# ETHERNET.net
KiCad netlist of a schematic drawn in Altium Designer
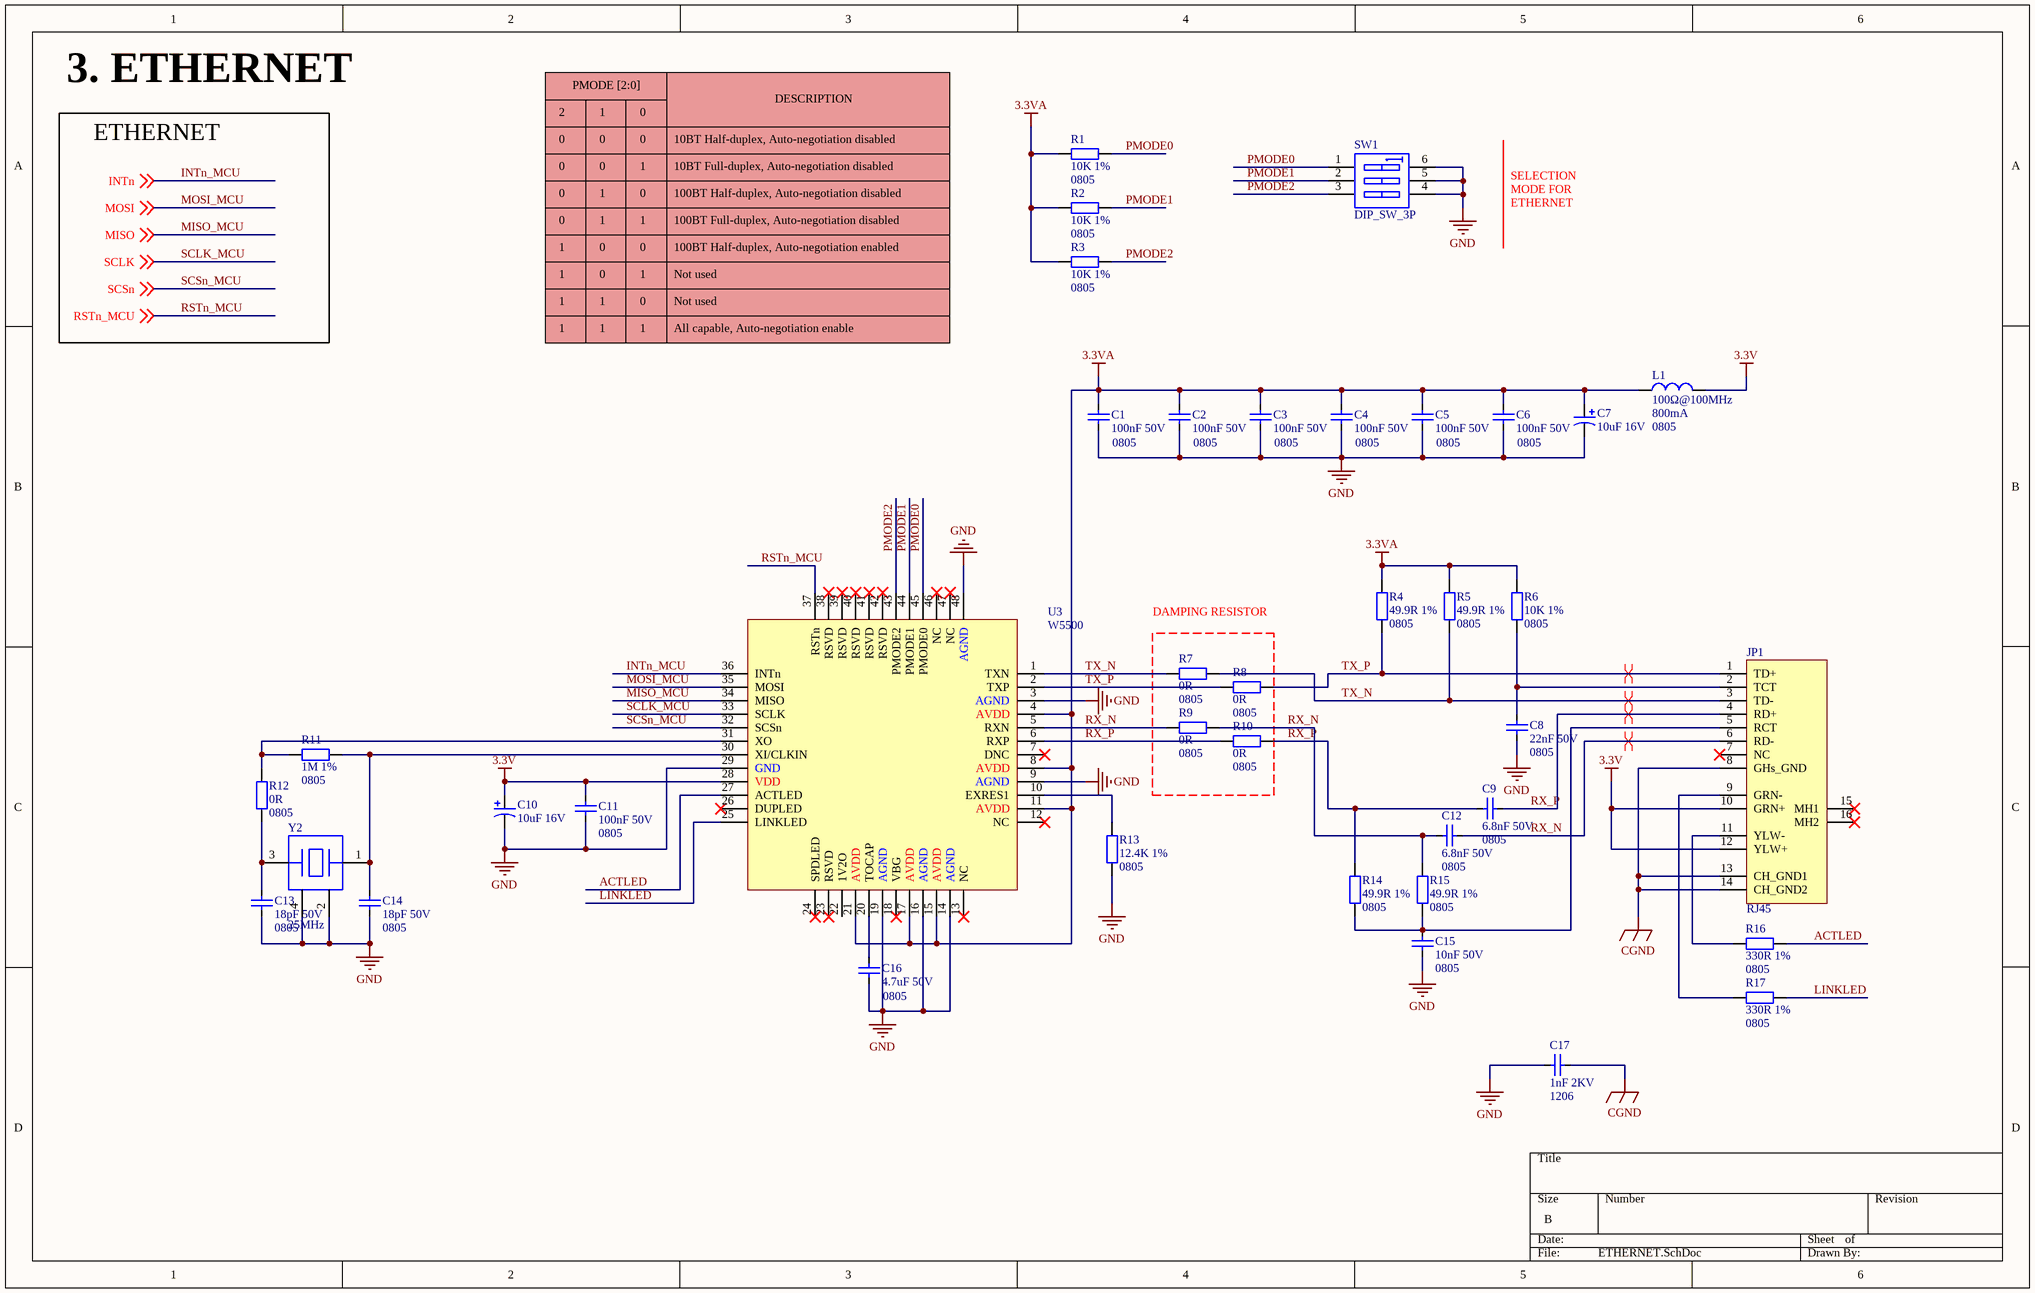
[diagram p0: ETHERNET.SchDoc]

(export (version "E")
  (design (tool "Eeschema 10.0.6"))
  (components
    (comp (ref "C1")
      (value "100nF 50V")
      (footprint "CAP_SMD_0805")
      (description "0.1 µF ±10% 50V Ceramic Capacitor X7R 0805 (2012 Metric)")
      (fields
        (field (name "MANUFACTURER") "YAGEO")
        (field (name "MANUFACTURE PART NUMBER") "CC0805KRX7R9BB104")
        (field (name "SIZE") "0805")
      )
      (libsource (lib "Capacitors") (part "C0805_MLCC_100nF_50V"))
    )
    (comp (ref "C2")
      (value "100nF 50V")
      (footprint "CAP_SMD_0805")
      (description "0.1 µF ±10% 50V Ceramic Capacitor X7R 0805 (2012 Metric)")
      (fields
        (field (name "MANUFACTURER") "YAGEO")
        (field (name "MANUFACTURE PART NUMBER") "CC0805KRX7R9BB104")
        (field (name "SIZE") "0805")
      )
      (libsource (lib "Capacitors") (part "C0805_MLCC_100nF_50V"))
    )
    (comp (ref "C3")
      (value "100nF 50V")
      (footprint "CAP_SMD_0805")
      (description "0.1 µF ±10% 50V Ceramic Capacitor X7R 0805 (2012 Metric)")
      (fields
        (field (name "MANUFACTURER") "YAGEO")
        (field (name "MANUFACTURE PART NUMBER") "CC0805KRX7R9BB104")
        (field (name "SIZE") "0805")
      )
      (libsource (lib "Capacitors") (part "C0805_MLCC_100nF_50V"))
    )
    (comp (ref "C4")
      (value "100nF 50V")
      (footprint "CAP_SMD_0805")
      (description "0.1 µF ±10% 50V Ceramic Capacitor X7R 0805 (2012 Metric)")
      (fields
        (field (name "MANUFACTURER") "YAGEO")
        (field (name "MANUFACTURE PART NUMBER") "CC0805KRX7R9BB104")
        (field (name "SIZE") "0805")
      )
      (libsource (lib "Capacitors") (part "C0805_MLCC_100nF_50V"))
    )
    (comp (ref "C5")
      (value "100nF 50V")
      (footprint "CAP_SMD_0805")
      (description "0.1 µF ±10% 50V Ceramic Capacitor X7R 0805 (2012 Metric)")
      (fields
        (field (name "MANUFACTURER") "YAGEO")
        (field (name "MANUFACTURE PART NUMBER") "CC0805KRX7R9BB104")
        (field (name "SIZE") "0805")
      )
      (libsource (lib "Capacitors") (part "C0805_MLCC_100nF_50V"))
    )
    (comp (ref "C6")
      (value "100nF 50V")
      (footprint "CAP_SMD_0805")
      (description "0.1 µF ±10% 50V Ceramic Capacitor X7R 0805 (2012 Metric)")
      (fields
        (field (name "MANUFACTURER") "YAGEO")
        (field (name "MANUFACTURE PART NUMBER") "CC0805KRX7R9BB104")
        (field (name "SIZE") "0805")
      )
      (libsource (lib "Capacitors") (part "C0805_MLCC_100nF_50V"))
    )
    (comp (ref "C7")
      (value "10uF 16V")
      (footprint "CAP-ALU-SMD-C")
      (description "10 µF 16 V Aluminum - Polymer Capacitors Radial, Can - SMD 30mOhm 2000 Hrs @ 105°C")
      (fields
        (field (name "MANUFACTURER") "Würth Elektronik")
        (field (name "MANUFACTURE PART NUMBER") "875105359001")
      )
      (libsource (lib "") (part "C_ALU_10uF_16V_1"))
    )
    (comp (ref "C8")
      (value "22nF 50V")
      (footprint "CAP_SMD_0805")
      (description "0.022 µF ±5% 50V Ceramic Capacitor C0G, NP0 0805 (2012 Metric)")
      (fields
        (field (name "MANUFACTURER") "TDK Corporation")
        (field (name "MANUFACTURE PART NUMBER") "CGA4J2C0G1H223J125AA")
        (field (name "SIZE") "0805")
      )
      (libsource (lib "Capacitors") (part "C0805_MLCC_22nF_50V"))
    )
    (comp (ref "C9")
      (value "6.8nF 50V")
      (footprint "CAP_SMD_0805")
      (description "6800 pF ±10% 50V Ceramic Capacitor X7R 0805 (2012 Metric)")
      (fields
        (field (name "MANUFACTURER") "KEMET")
        (field (name "MANUFACTURE PART NUMBER") "C0805C682K5RAC7800")
        (field (name "SIZE") "0805")
      )
      (libsource (lib "Capacitors") (part "C0805_MLCC_6.8nF_50V"))
    )
    (comp (ref "C10")
      (value "10uF 16V")
      (footprint "CAP-ALU-SMD-C")
      (description "10 µF 16 V Aluminum - Polymer Capacitors Radial, Can - SMD 30mOhm 2000 Hrs @ 105°C")
      (fields
        (field (name "MANUFACTURER") "Würth Elektronik")
        (field (name "MANUFACTURE PART NUMBER") "875105359001")
      )
      (libsource (lib "Capacitors") (part "C_ALU_10uF_16V"))
    )
    (comp (ref "C11")
      (value "100nF 50V")
      (footprint "CAP_SMD_0805")
      (description "0.1 µF ±10% 50V Ceramic Capacitor X7R 0805 (2012 Metric)")
      (fields
        (field (name "MANUFACTURER") "YAGEO")
        (field (name "MANUFACTURE PART NUMBER") "CC0805KRX7R9BB104")
        (field (name "SIZE") "0805")
      )
      (libsource (lib "Capacitors") (part "C0805_MLCC_100nF_50V"))
    )
    (comp (ref "C12")
      (value "6.8nF 50V")
      (footprint "CAP_SMD_0805")
      (description "6800 pF ±10% 50V Ceramic Capacitor X7R 0805 (2012 Metric)")
      (fields
        (field (name "MANUFACTURER") "KEMET")
        (field (name "MANUFACTURE PART NUMBER") "C0805C682K5RAC7800")
        (field (name "SIZE") "0805")
      )
      (libsource (lib "Capacitors") (part "C0805_MLCC_6.8nF_50V"))
    )
    (comp (ref "C13")
      (value "18pF 50V")
      (footprint "CAP_SMD_0805")
      (description "Multilayer Ceramic Capacitors MLCC - SMD/SMT 50V 18pF C0G 0805 1%")
      (fields
        (field (name "MANUFACTURER") "KEMET")
        (field (name "MANUFACTURE PART NUMBER") "C0805C180F5GACTU")
        (field (name "SIZE") "0805")
      )
      (libsource (lib "Capacitors") (part "C0805_MLCC_18pF_50V"))
    )
    (comp (ref "C14")
      (value "18pF 50V")
      (footprint "CAP_SMD_0805")
      (description "Multilayer Ceramic Capacitors MLCC - SMD/SMT 50V 18pF C0G 0805 1%")
      (fields
        (field (name "MANUFACTURER") "KEMET")
        (field (name "MANUFACTURE PART NUMBER") "C0805C180F5GACTU")
        (field (name "SIZE") "0805")
      )
      (libsource (lib "Capacitors") (part "C0805_MLCC_18pF_50V"))
    )
    (comp (ref "C15")
      (value "10nF 50V")
      (footprint "CAP_SMD_0805")
      (description "10000 pF ±10% 50V Ceramic Capacitor X7R 0805 (2012 Metric)")
      (fields
        (field (name "MANUFACTURER") "Samsung Electro-Mechanics")
        (field (name "MANUFACTURE PART NUMBER") "CL21B103KBANNNC")
        (field (name "SIZE") "0805")
      )
      (libsource (lib "Capacitors") (part "C0805_MLCC_10nF_50V"))
    )
    (comp (ref "C16")
      (value "4.7uF 50V")
      (footprint "CAP_SMD_0805")
      (description "4.7 µF ±10% 50V Ceramic Capacitor X5R 0805 (2012 Metric)")
      (fields
        (field (name "MANUFACTURER") "Samsung Electro-Mechanics")
        (field (name "MANUFACTURE PART NUMBER") "CL21A475KBQNNNE")
        (field (name "SIZE") "0805")
      )
      (libsource (lib "Capacitors") (part "C0805_MLCC_4.7uF_50V"))
    )
    (comp (ref "C17")
      (value "1nF 2KV")
      (footprint "CAP_SMD_0805")
      (description "1000 pF ±5% 2000V (2kV) Ceramic Capacitor X7R 1206 (3216 Metric)")
      (fields
        (field (name "MANUFACTURER") "YAGEO")
        (field (name "MANUFACTURE PART NUMBER") "CC1206JKX7RDBB102")
        (field (name "SIZE") "1206")
      )
      (libsource (lib "Capacitors") (part "C1206_MLCC_1nF_2KV"))
    )
    (comp (ref "JP1")
      (value "RJ45")
      (footprint "RJ 45")
      (description "1 Port RJ45Through Hole 10/100 Base-T, AutoMDIX")
      (fields (field (name "MANUFACTURER") "WIZnet") (field (name "MANUFACTURE PART NUMBER") "1278-1052-ND"))
      (libsource (lib "Connectors") (part "RJ45"))
    )
    (comp (ref "L1")
      (value "100Ohms 100Mhz")
      (footprint "FB_0805")
      (fields
        (field (name "MANUFACTURER") "TAI-TECH")
        (field (name "MANUFACTURE PART NUMBER") "FCM2012KF-101T08")
        (field (name "IMPEDANCE @ FREQUENCY") "100Ω@100MHz")
        (field (name "CURRENT") "800mA")
        (field (name "SIZE") "0805")
      )
      (libsource (lib "Inductors") (part "FR_100Ohms_100Mhz"))
    )
    (comp (ref "R1")
      (value "10K 1%")
      (footprint "RES_SMD_0805")
      (description "10 kOhms ±1% 0.125W, 1/8W Chip Resistor 0805 (2012 Metric) Moisture Resistant Thick Film")
      (fields
        (field (name "MANUFACTURER") "YAGEO")
        (field (name "MANUFACTURE PART NUMBER") "RC0805FR-0710KL")
        (field (name "SIZE") "0805")
      )
      (libsource (lib "Resistors") (part "R0805_10K"))
    )
    (comp (ref "R2")
      (value "10K 1%")
      (footprint "RES_SMD_0805")
      (description "10 kOhms ±1% 0.125W, 1/8W Chip Resistor 0805 (2012 Metric) Moisture Resistant Thick Film")
      (fields
        (field (name "MANUFACTURER") "YAGEO")
        (field (name "MANUFACTURE PART NUMBER") "RC0805FR-0710KL")
        (field (name "SIZE") "0805")
      )
      (libsource (lib "Resistors") (part "R0805_10K"))
    )
    (comp (ref "R3")
      (value "10K 1%")
      (footprint "RES_SMD_0805")
      (description "10 kOhms ±1% 0.125W, 1/8W Chip Resistor 0805 (2012 Metric) Moisture Resistant Thick Film")
      (fields
        (field (name "MANUFACTURER") "YAGEO")
        (field (name "MANUFACTURE PART NUMBER") "RC0805FR-0710KL")
        (field (name "SIZE") "0805")
      )
      (libsource (lib "Resistors") (part "R0805_10K"))
    )
    (comp (ref "R4")
      (value "49.9R 1%")
      (footprint "RES_SMD_0805")
      (description "49.9 Ohms ±1% 0.125W, 1/8W Chip Resistor 0805 (2012 Metric) Automotive AEC-Q200 Thick Film")
      (fields
        (field (name "MANUFACTURER") "Stackpole Electronics Inc")
        (field (name "MANUFACTURE PART NUMBER") "RMCF0805FT49R9")
        (field (name "SIZE") "0805")
      )
      (libsource (lib "Resistors") (part "R0805_49.9R"))
    )
    (comp (ref "R5")
      (value "49.9R 1%")
      (footprint "RES_SMD_0805")
      (description "49.9 Ohms ±1% 0.125W, 1/8W Chip Resistor 0805 (2012 Metric) Automotive AEC-Q200 Thick Film")
      (fields
        (field (name "MANUFACTURER") "Stackpole Electronics Inc")
        (field (name "MANUFACTURE PART NUMBER") "RMCF0805FT49R9")
        (field (name "SIZE") "0805")
      )
      (libsource (lib "Resistors") (part "R0805_49.9R"))
    )
    (comp (ref "R6")
      (value "10K 1%")
      (footprint "RES_SMD_0805")
      (description "10 kOhms ±1% 0.125W, 1/8W Chip Resistor 0805 (2012 Metric) Moisture Resistant Thick Film")
      (fields
        (field (name "MANUFACTURER") "YAGEO")
        (field (name "MANUFACTURE PART NUMBER") "RC0805FR-0710KL")
        (field (name "SIZE") "0805")
      )
      (libsource (lib "Resistors") (part "R0805_10K"))
    )
    (comp (ref "R7")
      (value "0R")
      (footprint "RES_SMD_0805")
      (description "0 Ohms Jumper Chip Resistor 0805 (2012 Metric) Automotive AEC-Q200 Thick Film")
      (fields
        (field (name "MANUFACTURER") "Vishay Dale")
        (field (name "MANUFACTURE PART NUMBER") "CRCW08050000Z0EA")
        (field (name "SIZE") "0805")
      )
      (libsource (lib "Resistors") (part "R0805_0R"))
    )
    (comp (ref "R8")
      (value "0R")
      (footprint "RES_SMD_0805")
      (description "0 Ohms Jumper Chip Resistor 0805 (2012 Metric) Automotive AEC-Q200 Thick Film")
      (fields
        (field (name "MANUFACTURER") "Vishay Dale")
        (field (name "MANUFACTURE PART NUMBER") "CRCW08050000Z0EA")
        (field (name "SIZE") "0805")
      )
      (libsource (lib "Resistors") (part "R0805_0R"))
    )
    (comp (ref "R9")
      (value "0R")
      (footprint "RES_SMD_0805")
      (description "0 Ohms Jumper Chip Resistor 0805 (2012 Metric) Automotive AEC-Q200 Thick Film")
      (fields
        (field (name "MANUFACTURER") "Vishay Dale")
        (field (name "MANUFACTURE PART NUMBER") "CRCW08050000Z0EA")
        (field (name "SIZE") "0805")
      )
      (libsource (lib "Resistors") (part "R0805_0R"))
    )
    (comp (ref "R10")
      (value "0R")
      (footprint "RES_SMD_0805")
      (description "0 Ohms Jumper Chip Resistor 0805 (2012 Metric) Automotive AEC-Q200 Thick Film")
      (fields
        (field (name "MANUFACTURER") "Vishay Dale")
        (field (name "MANUFACTURE PART NUMBER") "CRCW08050000Z0EA")
        (field (name "SIZE") "0805")
      )
      (libsource (lib "Resistors") (part "R0805_0R"))
    )
    (comp (ref "R11")
      (value "1M 1%")
      (footprint "RES_SMD_0805")
      (description "1 MOhms ±1% 0.125W, 1/8W Chip Resistor 0805 (2012 Metric) Automotive AEC-Q200 Thick Film")
      (fields
        (field (name "MANUFACTURER") "Stackpole Electronics Inc")
        (field (name "MANUFACTURE PART NUMBER") "RMCF0805FT1M00")
        (field (name "SIZE") "0805")
      )
      (libsource (lib "Resistors") (part "R0805_1M"))
    )
    (comp (ref "R12")
      (value "0R")
      (footprint "RES_SMD_0805")
      (description "0 Ohms Jumper Chip Resistor 0805 (2012 Metric) Automotive AEC-Q200 Thick Film")
      (fields
        (field (name "MANUFACTURER") "Vishay Dale")
        (field (name "MANUFACTURE PART NUMBER") "CRCW08050000Z0EA")
        (field (name "SIZE") "0805")
      )
      (libsource (lib "Resistors") (part "R0805_0R"))
    )
    (comp (ref "R13")
      (value "12.4K 1%")
      (footprint "RES_SMD_0805")
      (description "12.4 kOhms ±1% 0.125W, 1/8W Chip Resistor 0805 (2012 Metric) Automotive AEC-Q200 Thick Film")
      (fields
        (field (name "MANUFACTURER") "Stackpole Electronics Inc")
        (field (name "MANUFACTURE PART NUMBER") "RMCF0805FT12K4")
        (field (name "SIZE") "0805")
      )
      (libsource (lib "Resistors") (part "R0805_12.4K"))
    )
    (comp (ref "R14")
      (value "49.9R 1%")
      (footprint "RES_SMD_0805")
      (description "49.9 Ohms ±1% 0.125W, 1/8W Chip Resistor 0805 (2012 Metric) Automotive AEC-Q200 Thick Film")
      (fields
        (field (name "MANUFACTURER") "Stackpole Electronics Inc")
        (field (name "MANUFACTURE PART NUMBER") "RMCF0805FT49R9")
        (field (name "SIZE") "0805")
      )
      (libsource (lib "Resistors") (part "R0805_49.9R"))
    )
    (comp (ref "R15")
      (value "49.9R 1%")
      (footprint "RES_SMD_0805")
      (description "49.9 Ohms ±1% 0.125W, 1/8W Chip Resistor 0805 (2012 Metric) Automotive AEC-Q200 Thick Film")
      (fields
        (field (name "MANUFACTURER") "Stackpole Electronics Inc")
        (field (name "MANUFACTURE PART NUMBER") "RMCF0805FT49R9")
        (field (name "SIZE") "0805")
      )
      (libsource (lib "Resistors") (part "R0805_49.9R"))
    )
    (comp (ref "R16")
      (value "330R 1%")
      (footprint "RES_SMD_0805")
      (description "330 Ohms ±1% 0.125W, 1/8W Chip Resistor 0805 (2012 Metric) Automotive AEC-Q200 Thick Film")
      (fields
        (field (name "MANUFACTURER") "Stackpole Electronics Inc")
        (field (name "MANUFACTURE PART NUMBER") "RMCF0805FT330R")
        (field (name "SIZE") "0805")
      )
      (libsource (lib "Resistors") (part "R0805_330R"))
    )
    (comp (ref "R17")
      (value "330R 1%")
      (footprint "RES_SMD_0805")
      (description "330 Ohms ±1% 0.125W, 1/8W Chip Resistor 0805 (2012 Metric) Automotive AEC-Q200 Thick Film")
      (fields
        (field (name "MANUFACTURER") "Stackpole Electronics Inc")
        (field (name "MANUFACTURE PART NUMBER") "RMCF0805FT330R")
        (field (name "SIZE") "0805")
      )
      (libsource (lib "Resistors") (part "R0805_330R"))
    )
    (comp (ref "SW1")
      (value "DIP_SW_3P")
      (footprint "DIPSWITCH3")
      (description "Dip Switch SPST 3 Position Through Hole Slide (Standard) Actuator 25mA 24VDC")
      (fields
        (field (name "MANUFACTURER") "CIT Relay and Switch")
        (field (name "MANUFACTURE PART NUMBER") "KG03E")
      )
      (libsource (lib "Button") (part "DIP_SW_3P"))
    )
    (comp (ref "U3")
      (value "W5500")
      (footprint "LQFP 48")
      (description "Ethernet ICs 3in1 Enet Controller TCP/IP +MAC+PHY")
      (fields (field (name "MANUFACTURER") "WIZnet"))
      (libsource (lib "ICs") (part "W5500"))
    )
    (comp (ref "Y2")
      (value "25MHz")
      (footprint "SMD-3225_4P")
      (description "3.3V HCMOS ±4.6ppm 25MHz SMD3225-4P Temperature Compensated Crystal Oscillators (TCXOs) ROHS")
      (fields
        (field (name "MANUFACTURER") "HCI")
        (field (name "MANUFACTURE PART NUMBER") "TC32H4-25.000-33GNDTNL")
      )
      (libsource (lib "Crystal") (part "C3225_25MHz"))
    )
  )
  (nets
    (net (code "1") (name "/ACTLED") (class "Default")
      (node (ref "R16") (pin "2") (pinfunction "2_2") (pintype "passive"))
      (node (ref "U3") (pin "27") (pinfunction "ACTLED_27") (pintype "passive"))
    )
    (net (code "2") (name "/LINKLED") (class "Default")
      (node (ref "R17") (pin "2") (pinfunction "2_2") (pintype "passive"))
      (node (ref "U3") (pin "25") (pinfunction "LINKLED_25") (pintype "passive"))
    )
    (net (code "3") (name "/PMODE0") (class "Default")
      (node (ref "R1") (pin "1") (pinfunction "1_1") (pintype "passive"))
      (node (ref "SW1") (pin "1") (pinfunction "A1_1") (pintype "passive"))
      (node (ref "U3") (pin "45") (pinfunction "PMODE0_45") (pintype "passive"))
    )
    (net (code "4") (name "/PMODE1") (class "Default")
      (node (ref "R2") (pin "1") (pinfunction "1_1") (pintype "passive"))
      (node (ref "SW1") (pin "2") (pinfunction "A2_2") (pintype "passive"))
      (node (ref "U3") (pin "44") (pinfunction "PMODE1_44") (pintype "passive"))
    )
    (net (code "5") (name "/PMODE2") (class "Default")
      (node (ref "R3") (pin "1") (pinfunction "1_1") (pintype "passive"))
      (node (ref "SW1") (pin "3") (pinfunction "A3_3") (pintype "passive"))
      (node (ref "U3") (pin "43") (pinfunction "PMODE2_43") (pintype "passive"))
    )
    (net (code "6") (name "/RX_N") (class "Default")
      (node (ref "C12") (pin "1") (pinfunction "1_1") (pintype "passive"))
      (node (ref "C12") (pin "2") (pinfunction "2_2") (pintype "passive"))
      (node (ref "JP1") (pin "6") (pinfunction "RD-_6") (pintype "passive"))
      (node (ref "R15") (pin "2") (pinfunction "2_2") (pintype "passive"))
      (node (ref "R9") (pin "1") (pinfunction "1_1") (pintype "passive"))
      (node (ref "R9") (pin "2") (pinfunction "2_2") (pintype "passive"))
      (node (ref "U3") (pin "5") (pinfunction "RXN_5") (pintype "passive"))
    )
    (net (code "7") (name "/RX_P") (class "Default")
      (node (ref "C9") (pin "1") (pinfunction "1_1") (pintype "passive"))
      (node (ref "C9") (pin "2") (pinfunction "2_2") (pintype "passive"))
      (node (ref "JP1") (pin "4") (pinfunction "RD+_4") (pintype "passive"))
      (node (ref "R10") (pin "1") (pinfunction "1_1") (pintype "passive"))
      (node (ref "R10") (pin "2") (pinfunction "2_2") (pintype "passive"))
      (node (ref "R14") (pin "2") (pinfunction "2_2") (pintype "passive"))
      (node (ref "U3") (pin "6") (pinfunction "RXP_6") (pintype "passive"))
    )
    (net (code "8") (name "/TX_N") (class "Default")
      (node (ref "JP1") (pin "3") (pinfunction "TD-_3") (pintype "passive"))
      (node (ref "R5") (pin "1") (pinfunction "1_1") (pintype "passive"))
      (node (ref "R7") (pin "1") (pinfunction "1_1") (pintype "passive"))
      (node (ref "R7") (pin "2") (pinfunction "2_2") (pintype "passive"))
      (node (ref "U3") (pin "1") (pinfunction "TXN_1") (pintype "passive"))
    )
    (net (code "9") (name "/TX_P") (class "Default")
      (node (ref "JP1") (pin "1") (pinfunction "TD+_1") (pintype "passive"))
      (node (ref "R4") (pin "1") (pinfunction "1_1") (pintype "passive"))
      (node (ref "R8") (pin "1") (pinfunction "1_1") (pintype "passive"))
      (node (ref "R8") (pin "2") (pinfunction "2_2") (pintype "passive"))
      (node (ref "U3") (pin "2") (pinfunction "TXP_2") (pintype "passive"))
    )
    (net (code "10") (name "3.3V") (class "Default")
      (node (ref "C10") (pin "1") (pinfunction "1_1") (pintype "passive"))
      (node (ref "C11") (pin "2") (pinfunction "2_2") (pintype "passive"))
      (node (ref "JP1") (pin "10") (pinfunction "GRN+_10") (pintype "passive"))
      (node (ref "JP1") (pin "12") (pinfunction "YLW+_12") (pintype "passive"))
      (node (ref "L1") (pin "2") (pinfunction "2_2") (pintype "passive"))
      (node (ref "U3") (pin "28") (pinfunction "VDD_28") (pintype "passive"))
    )
    (net (code "11") (name "3.3VA") (class "Default")
      (node (ref "C1") (pin "2") (pinfunction "2_2") (pintype "passive"))
      (node (ref "C2") (pin "2") (pinfunction "2_2") (pintype "passive"))
      (node (ref "C3") (pin "2") (pinfunction "2_2") (pintype "passive"))
      (node (ref "C4") (pin "2") (pinfunction "2_2") (pintype "passive"))
      (node (ref "C5") (pin "2") (pinfunction "2_2") (pintype "passive"))
      (node (ref "C6") (pin "2") (pinfunction "2_2") (pintype "passive"))
      (node (ref "C7") (pin "1") (pinfunction "1_1") (pintype "passive"))
      (node (ref "L1") (pin "1") (pinfunction "1_1") (pintype "passive"))
      (node (ref "R1") (pin "2") (pinfunction "2_2") (pintype "passive"))
      (node (ref "R2") (pin "2") (pinfunction "2_2") (pintype "passive"))
      (node (ref "R3") (pin "2") (pinfunction "2_2") (pintype "passive"))
      (node (ref "R4") (pin "2") (pinfunction "2_2") (pintype "passive"))
      (node (ref "R5") (pin "2") (pinfunction "2_2") (pintype "passive"))
      (node (ref "R6") (pin "2") (pinfunction "2_2") (pintype "passive"))
      (node (ref "U3") (pin "11") (pinfunction "AVDD_11") (pintype "passive"))
      (node (ref "U3") (pin "15") (pinfunction "AVDD_15") (pintype "passive"))
      (node (ref "U3") (pin "17") (pinfunction "AVDD_17") (pintype "passive"))
      (node (ref "U3") (pin "21") (pinfunction "AVDD_21") (pintype "passive"))
      (node (ref "U3") (pin "4") (pinfunction "AVDD_4") (pintype "passive"))
      (node (ref "U3") (pin "8") (pinfunction "AVDD_8") (pintype "passive"))
    )
    (net (code "12") (name "CGND") (class "Default")
      (node (ref "C17") (pin "2") (pinfunction "2_2") (pintype "passive"))
      (node (ref "JP1") (pin "13") (pinfunction "CH_GND1_13") (pintype "passive"))
      (node (ref "JP1") (pin "14") (pinfunction "CH_GND2_14") (pintype "passive"))
      (node (ref "JP1") (pin "8") (pinfunction "GHs_GND_8") (pintype "passive"))
    )
    (net (code "13") (name "GND") (class "Default")
      (node (ref "C1") (pin "1") (pinfunction "1_1") (pintype "passive"))
      (node (ref "C10") (pin "2") (pinfunction "2_2") (pintype "passive"))
      (node (ref "C11") (pin "1") (pinfunction "1_1") (pintype "passive"))
      (node (ref "C13") (pin "1") (pinfunction "1_1") (pintype "passive"))
      (node (ref "C14") (pin "1") (pinfunction "1_1") (pintype "passive"))
      (node (ref "C15") (pin "1") (pinfunction "1_1") (pintype "passive"))
      (node (ref "C16") (pin "1") (pinfunction "1_1") (pintype "passive"))
      (node (ref "C17") (pin "1") (pinfunction "1_1") (pintype "passive"))
      (node (ref "C2") (pin "1") (pinfunction "1_1") (pintype "passive"))
      (node (ref "C3") (pin "1") (pinfunction "1_1") (pintype "passive"))
      (node (ref "C4") (pin "1") (pinfunction "1_1") (pintype "passive"))
      (node (ref "C5") (pin "1") (pinfunction "1_1") (pintype "passive"))
      (node (ref "C6") (pin "1") (pinfunction "1_1") (pintype "passive"))
      (node (ref "C7") (pin "2") (pinfunction "2_2") (pintype "passive"))
      (node (ref "C8") (pin "1") (pinfunction "1_1") (pintype "passive"))
      (node (ref "R13") (pin "1") (pinfunction "1_1") (pintype "passive"))
      (node (ref "SW1") (pin "4") (pinfunction "B3_4") (pintype "passive"))
      (node (ref "SW1") (pin "5") (pinfunction "B2_5") (pintype "passive"))
      (node (ref "SW1") (pin "6") (pinfunction "B1_6") (pintype "passive"))
      (node (ref "U3") (pin "14") (pinfunction "AGND_14") (pintype "passive"))
      (node (ref "U3") (pin "16") (pinfunction "AGND_16") (pintype "passive"))
      (node (ref "U3") (pin "19") (pinfunction "AGND_19") (pintype "passive"))
      (node (ref "U3") (pin "29") (pinfunction "GND_29") (pintype "passive"))
      (node (ref "U3") (pin "3") (pinfunction "AGND_3") (pintype "passive"))
      (node (ref "U3") (pin "48") (pinfunction "AGND_48") (pintype "passive"))
      (node (ref "U3") (pin "9") (pinfunction "AGND_9") (pintype "passive"))
      (node (ref "Y2") (pin "2") (pinfunction "2_2") (pintype "passive"))
      (node (ref "Y2") (pin "4") (pinfunction "4_4") (pintype "passive"))
    )
    (net (code "14") (name "INTn") (class "Default")
      (node (ref "U3") (pin "36") (pinfunction "INTn_36") (pintype "passive"))
    )
    (net (code "15") (name "MISO") (class "Default")
      (node (ref "U3") (pin "34") (pinfunction "MISO_34") (pintype "passive"))
    )
    (net (code "16") (name "MOSI") (class "Default")
      (node (ref "U3") (pin "35") (pinfunction "MOSI_35") (pintype "passive"))
    )
    (net (code "17") (name "Net-(C13-Pad2)") (class "Default")
      (node (ref "C13") (pin "2") (pinfunction "2_2") (pintype "passive"))
      (node (ref "R12") (pin "1") (pinfunction "1_1") (pintype "passive"))
      (node (ref "Y2") (pin "3") (pinfunction "3_3") (pintype "passive"))
    )
    (net (code "18") (name "Net-(JP1-GRN-)") (class "Default")
      (node (ref "JP1") (pin "9") (pinfunction "GRN-_9") (pintype "passive"))
      (node (ref "R17") (pin "1") (pinfunction "1_1") (pintype "passive"))
    )
    (net (code "19") (name "Net-(JP1-RCT)") (class "Default")
      (node (ref "C15") (pin "2") (pinfunction "2_2") (pintype "passive"))
      (node (ref "JP1") (pin "5") (pinfunction "RCT_5") (pintype "passive"))
      (node (ref "R14") (pin "1") (pinfunction "1_1") (pintype "passive"))
      (node (ref "R15") (pin "1") (pinfunction "1_1") (pintype "passive"))
    )
    (net (code "20") (name "Net-(JP1-TCT)") (class "Default")
      (node (ref "C8") (pin "2") (pinfunction "2_2") (pintype "passive"))
      (node (ref "JP1") (pin "2") (pinfunction "TCT_2") (pintype "passive"))
      (node (ref "R6") (pin "1") (pinfunction "1_1") (pintype "passive"))
    )
    (net (code "21") (name "Net-(JP1-YLW-)") (class "Default")
      (node (ref "JP1") (pin "11") (pinfunction "YLW-_11") (pintype "passive"))
      (node (ref "R16") (pin "1") (pinfunction "1_1") (pintype "passive"))
    )
    (net (code "22") (name "Net-(U3-EXRES1)") (class "Default")
      (node (ref "R13") (pin "2") (pinfunction "2_2") (pintype "passive"))
      (node (ref "U3") (pin "10") (pinfunction "EXRES1_10") (pintype "passive"))
    )
    (net (code "23") (name "Net-(U3-TOCAP)") (class "Default")
      (node (ref "C16") (pin "2") (pinfunction "2_2") (pintype "passive"))
      (node (ref "U3") (pin "20") (pinfunction "TOCAP_20") (pintype "passive"))
    )
    (net (code "24") (name "Net-(U3-XI{slash}CLKIN)") (class "Default")
      (node (ref "C14") (pin "2") (pinfunction "2_2") (pintype "passive"))
      (node (ref "R11") (pin "2") (pinfunction "2_2") (pintype "passive"))
      (node (ref "U3") (pin "30") (pinfunction "XI/CLKIN_30") (pintype "passive"))
      (node (ref "Y2") (pin "1") (pinfunction "1_1") (pintype "passive"))
    )
    (net (code "25") (name "Net-(U3-XO)") (class "Default")
      (node (ref "R11") (pin "1") (pinfunction "1_1") (pintype "passive"))
      (node (ref "R12") (pin "2") (pinfunction "2_2") (pintype "passive"))
      (node (ref "U3") (pin "31") (pinfunction "XO_31") (pintype "passive"))
    )
    (net (code "26") (name "RSTn_MCU") (class "Default")
      (node (ref "U3") (pin "37") (pinfunction "RSTn_37") (pintype "passive"))
    )
    (net (code "27") (name "SCLK") (class "Default")
      (node (ref "U3") (pin "33") (pinfunction "SCLK_33") (pintype "passive"))
    )
    (net (code "28") (name "SCSn") (class "Default")
      (node (ref "U3") (pin "32") (pinfunction "SCSn_32") (pintype "passive"))
    )
    (net (code "29") (name "unconnected-(JP1-MH1-Pad15)") (class "Default")
      (node (ref "JP1") (pin "15") (pinfunction "MH1_15") (pintype "passive+no_connect"))
    )
    (net (code "30") (name "unconnected-(JP1-MH2-Pad16)") (class "Default")
      (node (ref "JP1") (pin "16") (pinfunction "MH2_16") (pintype "passive+no_connect"))
    )
    (net (code "31") (name "unconnected-(JP1-NC-Pad7)") (class "Default")
      (node (ref "JP1") (pin "7") (pinfunction "NC_7") (pintype "passive+no_connect"))
    )
    (net (code "32") (name "unconnected-(U3-1V2O-Pad22)") (class "Default")
      (node (ref "U3") (pin "22") (pinfunction "1V2O_22") (pintype "passive"))
    )
    (net (code "33") (name "unconnected-(U3-DNC-Pad7)") (class "Default")
      (node (ref "U3") (pin "7") (pinfunction "DNC_7") (pintype "passive+no_connect"))
    )
    (net (code "34") (name "unconnected-(U3-DUPLED-Pad26)") (class "Default")
      (node (ref "U3") (pin "26") (pinfunction "DUPLED_26") (pintype "passive+no_connect"))
    )
    (net (code "35") (name "unconnected-(U3-NC-Pad12)") (class "Default")
      (node (ref "U3") (pin "12") (pinfunction "NC_12") (pintype "passive+no_connect"))
    )
    (net (code "36") (name "unconnected-(U3-NC-Pad13)") (class "Default")
      (node (ref "U3") (pin "13") (pinfunction "NC_13") (pintype "passive+no_connect"))
    )
    (net (code "37") (name "unconnected-(U3-NC-Pad46)") (class "Default")
      (node (ref "U3") (pin "46") (pinfunction "NC_46") (pintype "passive+no_connect"))
    )
    (net (code "38") (name "unconnected-(U3-NC-Pad47)") (class "Default")
      (node (ref "U3") (pin "47") (pinfunction "NC_47") (pintype "passive+no_connect"))
    )
    (net (code "39") (name "unconnected-(U3-RSVD-Pad23)") (class "Default")
      (node (ref "U3") (pin "23") (pinfunction "RSVD_23") (pintype "passive+no_connect"))
    )
    (net (code "40") (name "unconnected-(U3-RSVD-Pad38)") (class "Default")
      (node (ref "U3") (pin "38") (pinfunction "RSVD_38") (pintype "passive+no_connect"))
    )
    (net (code "41") (name "unconnected-(U3-RSVD-Pad39)") (class "Default")
      (node (ref "U3") (pin "39") (pinfunction "RSVD_39") (pintype "passive+no_connect"))
    )
    (net (code "42") (name "unconnected-(U3-RSVD-Pad40)") (class "Default")
      (node (ref "U3") (pin "40") (pinfunction "RSVD_40") (pintype "passive+no_connect"))
    )
    (net (code "43") (name "unconnected-(U3-RSVD-Pad41)") (class "Default")
      (node (ref "U3") (pin "41") (pinfunction "RSVD_41") (pintype "passive+no_connect"))
    )
    (net (code "44") (name "unconnected-(U3-RSVD-Pad42)") (class "Default")
      (node (ref "U3") (pin "42") (pinfunction "RSVD_42") (pintype "passive+no_connect"))
    )
    (net (code "45") (name "unconnected-(U3-SPDLED-Pad24)") (class "Default")
      (node (ref "U3") (pin "24") (pinfunction "SPDLED_24") (pintype "passive+no_connect"))
    )
    (net (code "46") (name "unconnected-(U3-VBG-Pad18)") (class "Default")
      (node (ref "U3") (pin "18") (pinfunction "VBG_18") (pintype "passive+no_connect"))
    )
  )
)
